# powerblade_v6_1_corr.net
KiCad netlist of a schematic drawn in EAGLE
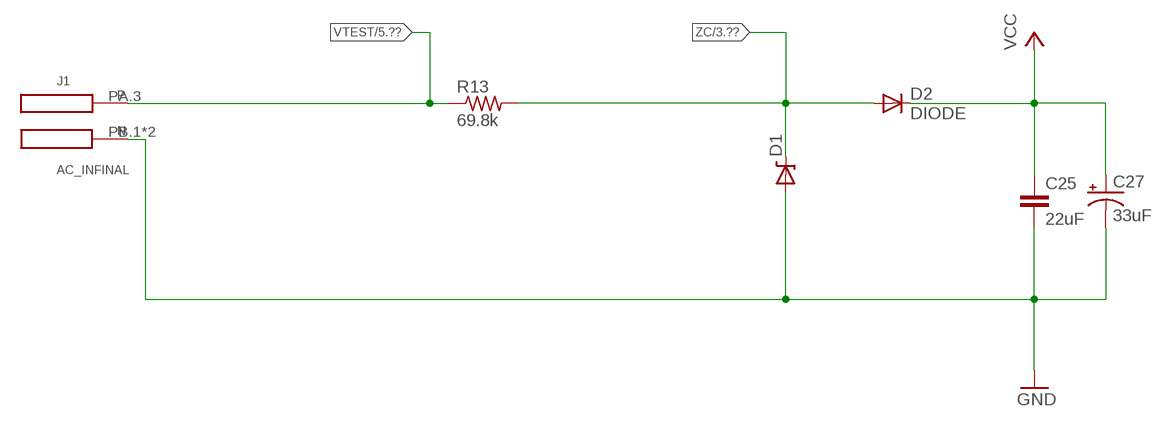
[diagram p0: schematic, sheet 1]
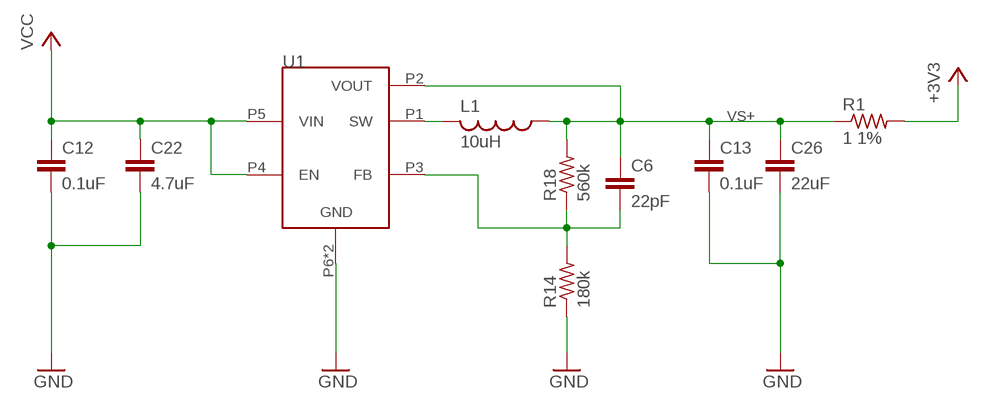
[diagram p1: schematic, sheet 2]
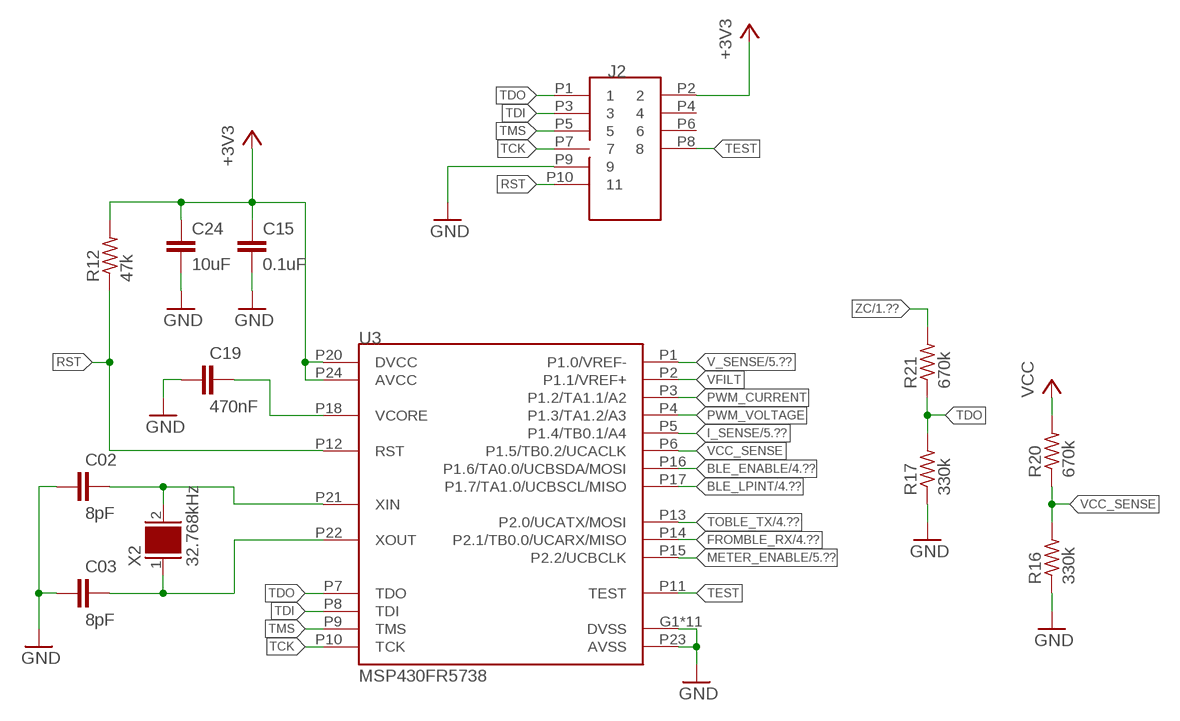
[diagram p2: schematic, sheet 3]
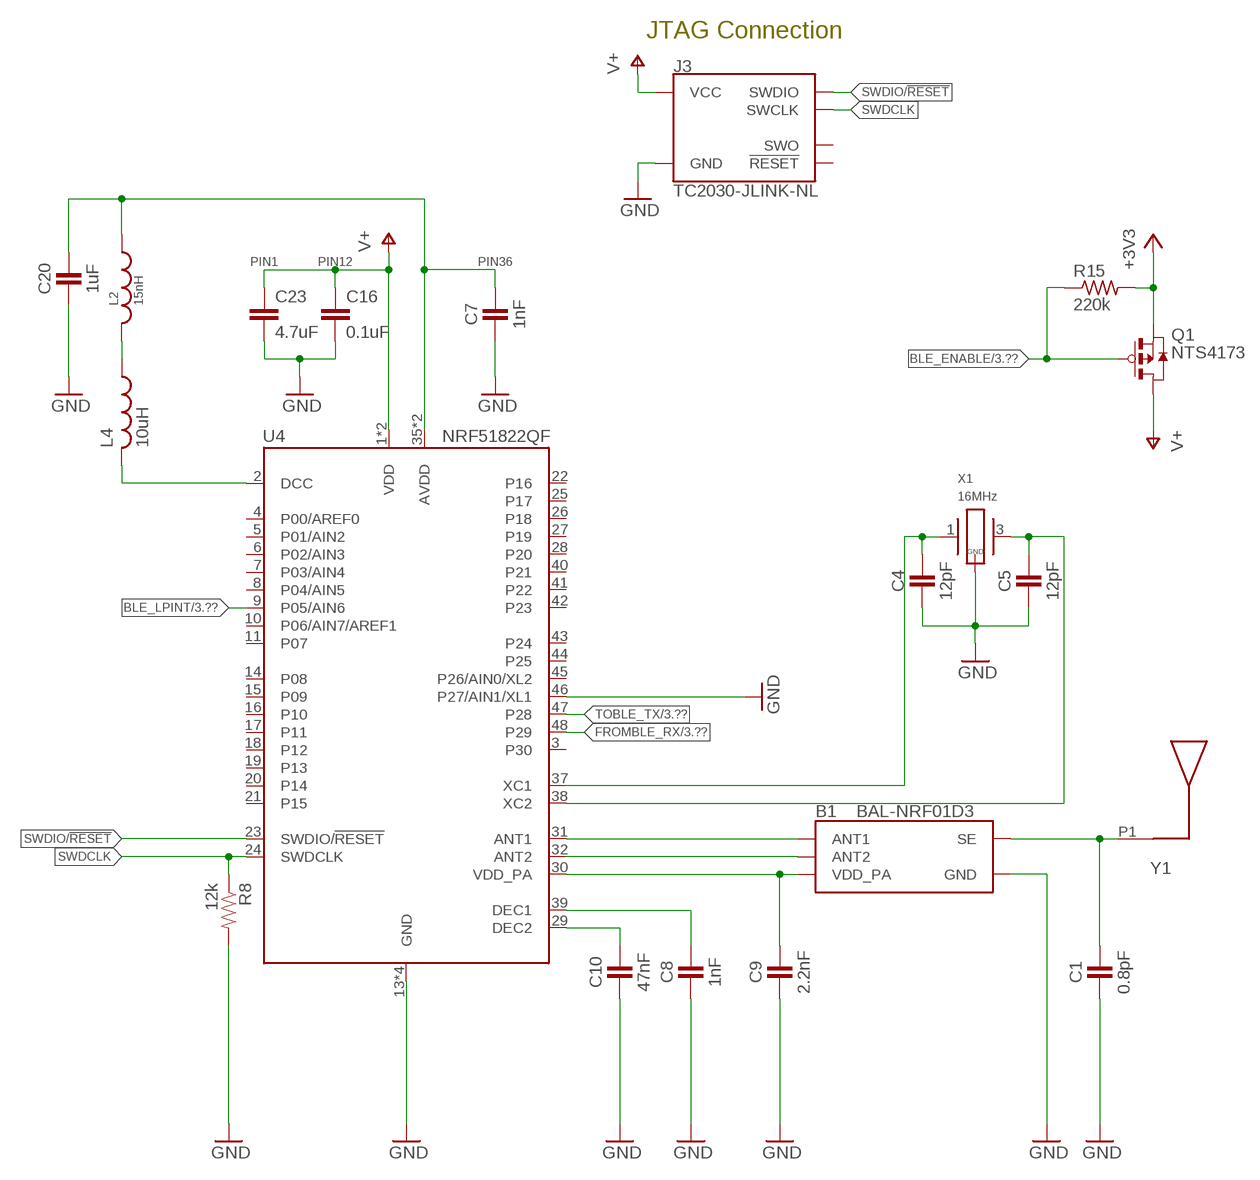
[diagram p3: schematic, sheet 4]
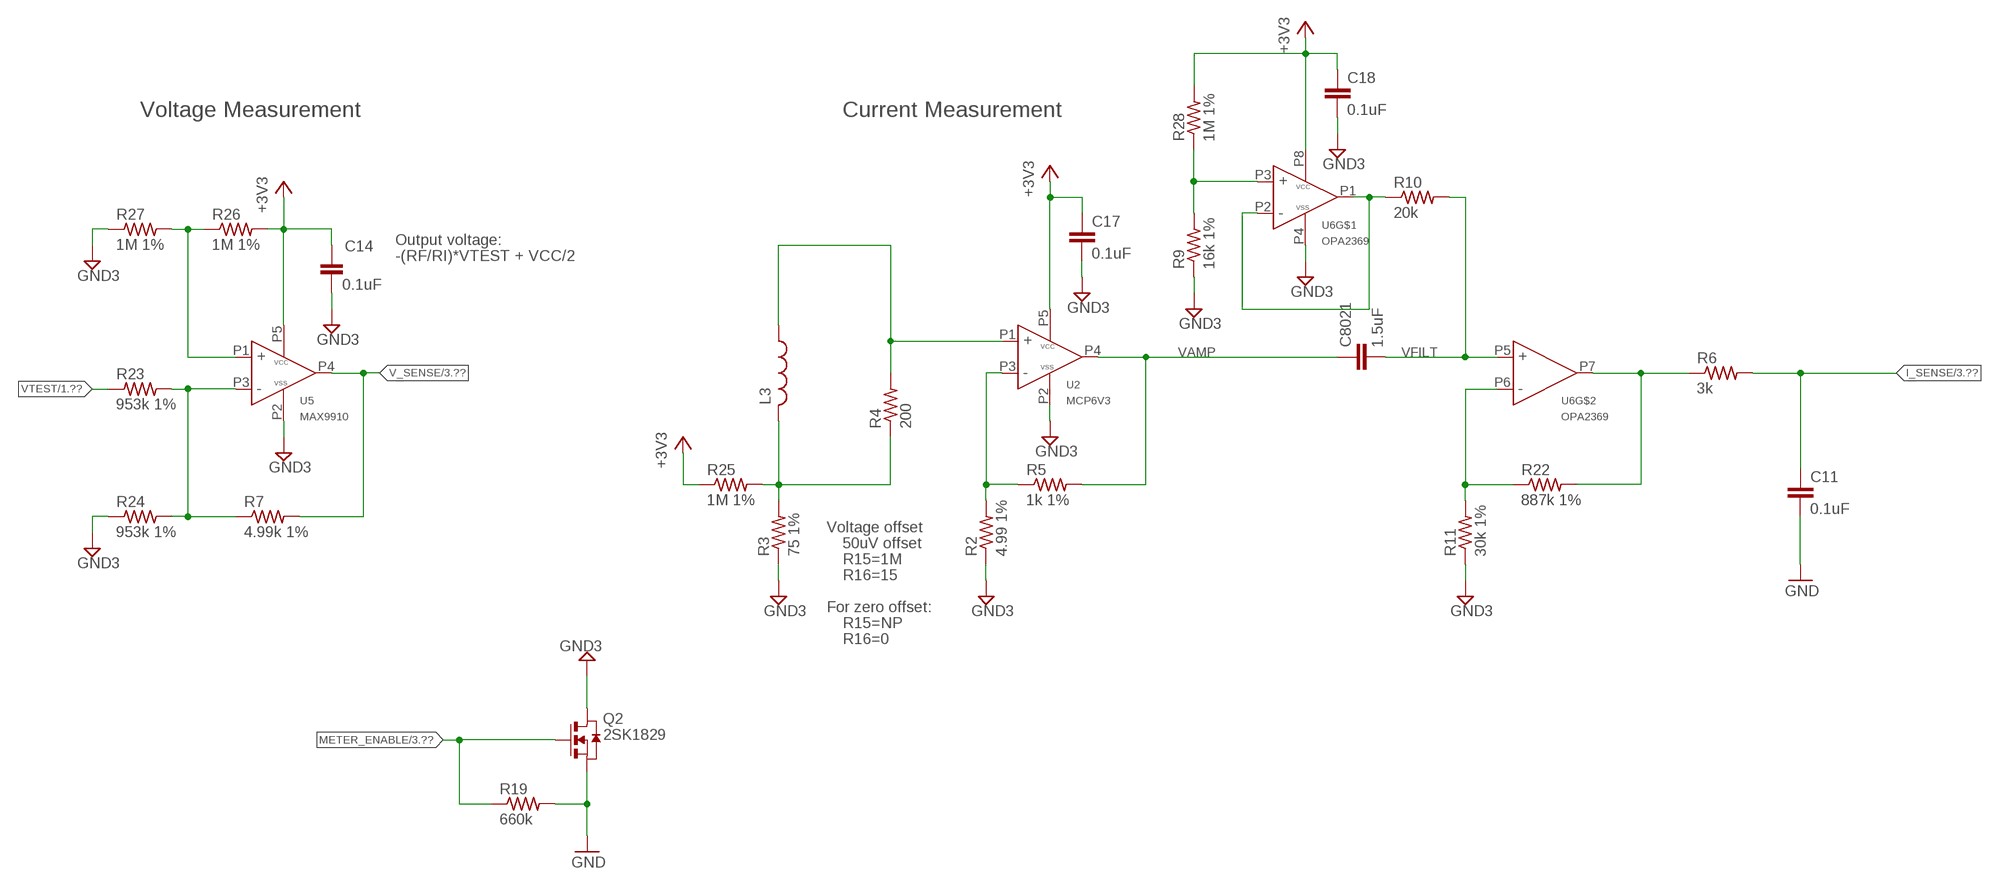
[diagram p4: schematic, sheet 5]

(export (version "E")
  (design (tool "Eeschema 10.0.6"))
  (components
    (comp (ref "C25")
      (value "22uF")
      (footprint "eagle-import:C0603_SM")
      (libsource (lib "eagle-import") (part "C-EUC0603_SM"))
    )
    (comp (ref "C27")
      (value "33uF")
      (footprint "eagle-import:CPOL0805_SM")
      (libsource (lib "eagle-import") (part "CPOL-US0805_SM"))
    )
    (comp (ref "D1")
      (value "ZENERBZT52")
      (footprint "eagle-import:BZT52")
      (fields (field (name "DIGIKEY") "BZT52C10T-7DICT-ND "))
      (libsource (lib "eagle-import") (part "ZENERBZT52"))
    )
    (comp (ref "D2")
      (value "DIODE")
      (footprint "eagle-import:BAS521")
      (libsource (lib "eagle-import") (part "DIODE"))
    )
    (comp (ref "J1")
      (value "AC_INFINAL")
      (footprint "eagle-import:AC3_FINAL")
      (libsource (lib "eagle-import") (part "AC_INFINAL"))
    )
    (comp (ref "R13")
      (value "69.8k")
      (footprint "eagle-import:R1210")
      (libsource (lib "eagle-import") (part "R-US_R1210"))
    )
    (comp (ref "B1")
      (value "BAL-NRF01D3")
      (footprint "eagle-import:BAL-NRF01D3")
      (libsource (lib "eagle-import") (part "BAL-NRF01D3"))
    )
    (comp (ref "C1")
      (value "0.8pF")
      (footprint "eagle-import:0402_CAP")
      (libsource (lib "eagle-import") (part "CAPACITOR"))
    )
    (comp (ref "C4")
      (value "12pF")
      (footprint "eagle-import:0402_CAP")
      (libsource (lib "eagle-import") (part "CAPACITOR"))
    )
    (comp (ref "C5")
      (value "12pF")
      (footprint "eagle-import:0402_CAP")
      (libsource (lib "eagle-import") (part "CAPACITOR"))
    )
    (comp (ref "C7")
      (value "1nF")
      (footprint "eagle-import:0402_CAP")
      (libsource (lib "eagle-import") (part "CAPACITOR"))
    )
    (comp (ref "C8")
      (value "1nF")
      (footprint "eagle-import:0402_CAP")
      (libsource (lib "eagle-import") (part "CAPACITOR"))
    )
    (comp (ref "C9")
      (value "2.2nF")
      (footprint "eagle-import:0402_CAP")
      (libsource (lib "eagle-import") (part "CAPACITOR"))
    )
    (comp (ref "C10")
      (value "47nF")
      (footprint "eagle-import:0402_CAP")
      (libsource (lib "eagle-import") (part "CAPACITOR"))
    )
    (comp (ref "C16")
      (value "0.1uF")
      (footprint "eagle-import:C0402")
      (libsource (lib "eagle-import") (part "C-EUC0402"))
    )
    (comp (ref "C20")
      (value "1uF")
      (footprint "eagle-import:0402_CAP")
      (libsource (lib "eagle-import") (part "CAPACITOR"))
    )
    (comp (ref "C23")
      (value "4.7uF")
      (footprint "eagle-import:C0402")
      (libsource (lib "eagle-import") (part "C-EUC0402"))
    )
    (comp (ref "J3")
      (value "TC2030-JLINK-NL")
      (footprint "eagle-import:TC2030-IDC-NL")
      (libsource (lib "eagle-import") (part "TC2030-JLINK-NL"))
    )
    (comp (ref "L2")
      (value "15nH")
      (footprint "eagle-import:0402_CAP")
      (libsource (lib "eagle-import") (part "INDUCTOR0402"))
    )
    (comp (ref "L4")
      (value "10uH")
      (footprint "eagle-import:C0603_TN")
      (libsource (lib "eagle-import") (part "L-USL0603_TN"))
    )
    (comp (ref "Q1")
      (value "NTS4173")
      (footprint "eagle-import:SC-70-3")
      (libsource (lib "eagle-import") (part "NTS4173"))
    )
    (comp (ref "R8")
      (value "12k")
      (footprint "eagle-import:0402_RES")
      (libsource (lib "eagle-import") (part "RESISTOR"))
    )
    (comp (ref "R15")
      (value "220k")
      (footprint "eagle-import:R0402_SM")
      (libsource (lib "eagle-import") (part "R-US_R0402_SM"))
    )
    (comp (ref "U4")
      (value "NRF51822QF")
      (footprint "eagle-import:QFN-48-6MM")
      (libsource (lib "eagle-import") (part "NRF51822QF"))
    )
    (comp (ref "X1")
      (value "16MHz")
      (footprint "eagle-import:TXC-8Y")
      (libsource (lib "eagle-import") (part "TXC-8Y"))
    )
    (comp (ref "Y1")
      (value "UREACH_XTEND")
      (footprint "eagle-import:UREACH_XTEND")
      (libsource (lib "eagle-import") (part "UREACH_XTEND"))
    )
    (comp (ref "C02")
      (value "8pF")
      (footprint "eagle-import:C0402")
      (libsource (lib "eagle-import") (part "C-EUC0402"))
    )
    (comp (ref "C03")
      (value "8pF")
      (footprint "eagle-import:C0402")
      (libsource (lib "eagle-import") (part "C-EUC0402"))
    )
    (comp (ref "C15")
      (value "0.1uF")
      (footprint "eagle-import:C0402")
      (libsource (lib "eagle-import") (part "C-EUC0402"))
    )
    (comp (ref "C19")
      (value "470nF")
      (footprint "eagle-import:C0402")
      (libsource (lib "eagle-import") (part "C-EUC0402"))
    )
    (comp (ref "C24")
      (value "10uF")
      (footprint "eagle-import:C0603_SM")
      (libsource (lib "eagle-import") (part "C-EUC0603_SM"))
    )
    (comp (ref "J2")
      (value "JTAG_14PIN_IDC-ND")
      (footprint "eagle-import:TC2050-IDC-NL-430-ND")
      (libsource (lib "eagle-import") (part "JTAG_14PIN_IDC-ND"))
    )
    (comp (ref "R12")
      (value "47k")
      (footprint "eagle-import:R0402")
      (libsource (lib "eagle-import") (part "R-US_R0402"))
    )
    (comp (ref "R16")
      (value "330k")
      (footprint "eagle-import:R0402")
      (libsource (lib "eagle-import") (part "R-US_R0402"))
    )
    (comp (ref "R17")
      (value "330k")
      (footprint "eagle-import:R0402")
      (libsource (lib "eagle-import") (part "R-US_R0402"))
    )
    (comp (ref "R20")
      (value "670k")
      (footprint "eagle-import:R0402")
      (libsource (lib "eagle-import") (part "R-US_R0402"))
    )
    (comp (ref "R21")
      (value "670k")
      (footprint "eagle-import:R0402")
      (libsource (lib "eagle-import") (part "R-US_R0402"))
    )
    (comp (ref "U3")
      (value "MSP430FR5738")
      (footprint "eagle-import:VQFN-24")
      (libsource (lib "eagle-import") (part "MSP430FR5738"))
    )
    (comp (ref "X2")
      (value "32.768kHz")
      (footprint "eagle-import:0805")
      (libsource (lib "eagle-import") (part "CRYSTAL_0805"))
    )
    (comp (ref "C11")
      (value "0.1uF")
      (footprint "eagle-import:C0402")
      (libsource (lib "eagle-import") (part "C-EUC0402"))
    )
    (comp (ref "C14")
      (value "0.1uF")
      (footprint "eagle-import:0402_CAP")
      (libsource (lib "eagle-import") (part "CAPACITOR"))
    )
    (comp (ref "C17")
      (value "0.1uF")
      (footprint "eagle-import:C0402")
      (libsource (lib "eagle-import") (part "C-EUC0402"))
    )
    (comp (ref "C18")
      (value "0.1uF")
      (footprint "eagle-import:C0402")
      (libsource (lib "eagle-import") (part "C-EUC0402"))
    )
    (comp (ref "C8021")
      (value "1.5uF")
      (footprint "eagle-import:C0402")
      (libsource (lib "eagle-import") (part "C-EUC0402"))
    )
    (comp (ref "L3")
      (value "L-USL0805")
      (footprint "eagle-import:L0805")
      (libsource (lib "eagle-import") (part "L-USL0805"))
    )
    (comp (ref "Q2")
      (value "2SK1829")
      (footprint "eagle-import:SC-70-3")
      (libsource (lib "eagle-import") (part "2SK1829"))
    )
    (comp (ref "R2")
      (value "4.99 1%")
      (footprint "eagle-import:R0402")
      (libsource (lib "eagle-import") (part "R-US_R0402"))
    )
    (comp (ref "R3")
      (value "75 1%")
      (footprint "eagle-import:R0402")
      (libsource (lib "eagle-import") (part "R-US_R0402"))
    )
    (comp (ref "R4")
      (value "200")
      (footprint "eagle-import:R0402")
      (libsource (lib "eagle-import") (part "R-US_R0402"))
    )
    (comp (ref "R5")
      (value "1k 1%")
      (footprint "eagle-import:R0402")
      (libsource (lib "eagle-import") (part "R-US_R0402"))
    )
    (comp (ref "R6")
      (value "3k")
      (footprint "eagle-import:R0402_SM")
      (libsource (lib "eagle-import") (part "R-US_R0402_SM"))
    )
    (comp (ref "R7")
      (value "4.99k 1%")
      (footprint "eagle-import:R0402")
      (libsource (lib "eagle-import") (part "R-US_R0402"))
    )
    (comp (ref "R9")
      (value "16k 1%")
      (footprint "eagle-import:R0402")
      (libsource (lib "eagle-import") (part "R-US_R0402"))
    )
    (comp (ref "R10")
      (value "20k")
      (footprint "eagle-import:R0402")
      (libsource (lib "eagle-import") (part "R-US_R0402"))
    )
    (comp (ref "R11")
      (value "30k 1%")
      (footprint "eagle-import:R0402")
      (libsource (lib "eagle-import") (part "R-US_R0402"))
    )
    (comp (ref "R19")
      (value "660k")
      (footprint "eagle-import:R0402")
      (libsource (lib "eagle-import") (part "R-US_R0402"))
    )
    (comp (ref "R22")
      (value "887k 1%")
      (footprint "eagle-import:R0402")
      (libsource (lib "eagle-import") (part "R-US_R0402"))
    )
    (comp (ref "R23")
      (value "953k 1%")
      (footprint "eagle-import:R0402")
      (libsource (lib "eagle-import") (part "R-US_R0402"))
    )
    (comp (ref "R24")
      (value "953k 1%")
      (footprint "eagle-import:R0402")
      (libsource (lib "eagle-import") (part "R-US_R0402"))
    )
    (comp (ref "R25")
      (value "1M 1%")
      (footprint "eagle-import:R0402")
      (libsource (lib "eagle-import") (part "R-US_R0402"))
    )
    (comp (ref "R26")
      (value "1M 1%")
      (footprint "eagle-import:R0402")
      (libsource (lib "eagle-import") (part "R-US_R0402"))
    )
    (comp (ref "R27")
      (value "1M 1%")
      (footprint "eagle-import:R0402_SM")
      (libsource (lib "eagle-import") (part "R-US_R0402_SM"))
    )
    (comp (ref "R28")
      (value "1M 1%")
      (footprint "eagle-import:R0402")
      (libsource (lib "eagle-import") (part "R-US_R0402"))
    )
    (comp (ref "U2")
      (value "MCP6V3")
      (footprint "eagle-import:SC70-5")
      (fields (field (name "DIGIKEY") "296-19547-1-ND"))
      (libsource (lib "eagle-import") (part "MCP6V3"))
    )
    (comp (ref "U5")
      (value "MAX9910")
      (footprint "eagle-import:SC70-5")
      (fields (field (name "DIGIKEY") "296-25252-1-ND"))
      (libsource (lib "eagle-import") (part "MAX9910"))
    )
    (comp (ref "U6")
      (value "OPA2369")
      (footprint "eagle-import:SOT-23-8")
      (libsource (lib "eagle-import") (part "OPA2369"))
    )
    (comp (ref "C6")
      (value "22pF")
      (footprint "eagle-import:C0402")
      (libsource (lib "eagle-import") (part "C-EUC0402"))
    )
    (comp (ref "C12")
      (value "0.1uF")
      (footprint "eagle-import:C0402")
      (libsource (lib "eagle-import") (part "C-EUC0402"))
    )
    (comp (ref "C13")
      (value "0.1uF")
      (footprint "eagle-import:C0402_SM")
      (libsource (lib "eagle-import") (part "C-EUC0402_SM"))
    )
    (comp (ref "C22")
      (value "4.7uF")
      (footprint "eagle-import:C0402")
      (libsource (lib "eagle-import") (part "C-EUC0402"))
    )
    (comp (ref "C26")
      (value "22uF")
      (footprint "eagle-import:C0603_SM")
      (libsource (lib "eagle-import") (part "C-EUC0603_SM"))
    )
    (comp (ref "L1")
      (value "10uH")
      (footprint "eagle-import:L0805")
      (libsource (lib "eagle-import") (part "L-USL0805"))
    )
    (comp (ref "R1")
      (value "1 1%")
      (footprint "eagle-import:R0603_SM")
      (libsource (lib "eagle-import") (part "R-US_R0603_SM"))
    )
    (comp (ref "R14")
      (value "180k")
      (footprint "eagle-import:R0402")
      (libsource (lib "eagle-import") (part "R-US_R0402"))
    )
    (comp (ref "R18")
      (value "560k")
      (footprint "eagle-import:R0402")
      (libsource (lib "eagle-import") (part "R-US_R0402"))
    )
    (comp (ref "U1")
      (value "TPS62122")
      (footprint "eagle-import:WDFN-6")
      (libsource (lib "eagle-import") (part "TPS62122"))
    )
  )
  (nets
    (net (code "1") (name "+3V3") (class "Default")
      (node (ref "C14") (pin "1") (pinfunction "1_1") (pintype "bidirectional"))
      (node (ref "C15") (pin "1") (pinfunction "1_1") (pintype "passive"))
      (node (ref "C17") (pin "1") (pinfunction "1_1") (pintype "passive"))
      (node (ref "C18") (pin "1") (pinfunction "1_1") (pintype "passive"))
      (node (ref "C24") (pin "1") (pinfunction "1_1") (pintype "passive"))
      (node (ref "J2") (pin "P2") (pinfunction "2_P2") (pintype "bidirectional"))
      (node (ref "Q1") (pin "P2") (pinfunction "S_P2") (pintype "passive"))
      (node (ref "R1") (pin "2") (pinfunction "2_2") (pintype "passive"))
      (node (ref "R12") (pin "2") (pinfunction "2_2") (pintype "passive"))
      (node (ref "R15") (pin "2") (pinfunction "2_2") (pintype "passive"))
      (node (ref "R25") (pin "1") (pinfunction "1_1") (pintype "passive"))
      (node (ref "R26") (pin "2") (pinfunction "2_2") (pintype "passive"))
      (node (ref "R28") (pin "2") (pinfunction "2_2") (pintype "passive"))
      (node (ref "U2") (pin "P5") (pinfunction "VCC_P5") (pintype "bidirectional"))
      (node (ref "U3") (pin "P20") (pinfunction "DVCC_P20") (pintype "bidirectional"))
      (node (ref "U3") (pin "P24") (pinfunction "AVCC_P24") (pintype "bidirectional"))
      (node (ref "U5") (pin "P5") (pinfunction "VCC_P5") (pintype "bidirectional"))
      (node (ref "U6") (pin "P8") (pinfunction "VCC_P8") (pintype "bidirectional"))
    )
    (net (code "2") (name "BLE_ENABLE") (class "Default")
      (node (ref "Q1") (pin "P1") (pinfunction "G_P1") (pintype "passive"))
      (node (ref "R15") (pin "1") (pinfunction "1_1") (pintype "passive"))
      (node (ref "U3") (pin "P16") (pinfunction "P1.6/TA0.0/UCBSDA/MOSI_P16") (pintype "bidirectional"))
    )
    (net (code "3") (name "BLE_LPINT") (class "Default")
      (node (ref "U3") (pin "P17") (pinfunction "P1.7/TA1.0/UCBSCL/MISO_P17") (pintype "bidirectional"))
      (node (ref "U4") (pin "9") (pinfunction "P05/AIN6_9") (pintype "bidirectional"))
    )
    (net (code "4") (name "FROMBLE_RX") (class "Default")
      (node (ref "U3") (pin "P14") (pinfunction "P2.1/TB0.0/UCARX/MISO_P14") (pintype "bidirectional"))
      (node (ref "U4") (pin "48") (pinfunction "P29_48") (pintype "bidirectional"))
    )
    (net (code "5") (name "GND") (class "Default")
      (node (ref "B1") (pin "GND") (pinfunction "GND_GND") (pintype "bidirectional"))
      (node (ref "C02") (pin "1") (pinfunction "1_1") (pintype "passive"))
      (node (ref "C03") (pin "1") (pinfunction "1_1") (pintype "passive"))
      (node (ref "C1") (pin "2") (pinfunction "2_2") (pintype "bidirectional"))
      (node (ref "C10") (pin "2") (pinfunction "2_2") (pintype "bidirectional"))
      (node (ref "C11") (pin "2") (pinfunction "2_2") (pintype "passive"))
      (node (ref "C12") (pin "2") (pinfunction "2_2") (pintype "passive"))
      (node (ref "C13") (pin "2") (pinfunction "2_2") (pintype "passive"))
      (node (ref "C15") (pin "2") (pinfunction "2_2") (pintype "passive"))
      (node (ref "C16") (pin "2") (pinfunction "2_2") (pintype "passive"))
      (node (ref "C19") (pin "1") (pinfunction "1_1") (pintype "passive"))
      (node (ref "C20") (pin "2") (pinfunction "2_2") (pintype "bidirectional"))
      (node (ref "C22") (pin "2") (pinfunction "2_2") (pintype "passive"))
      (node (ref "C23") (pin "2") (pinfunction "2_2") (pintype "passive"))
      (node (ref "C24") (pin "2") (pinfunction "2_2") (pintype "passive"))
      (node (ref "C25") (pin "2") (pinfunction "2_2") (pintype "passive"))
      (node (ref "C26") (pin "2") (pinfunction "2_2") (pintype "passive"))
      (node (ref "C27") (pin "-") (pinfunction "-_-") (pintype "passive"))
      (node (ref "C4") (pin "2") (pinfunction "2_2") (pintype "bidirectional"))
      (node (ref "C5") (pin "2") (pinfunction "2_2") (pintype "bidirectional"))
      (node (ref "C7") (pin "2") (pinfunction "2_2") (pintype "bidirectional"))
      (node (ref "C8") (pin "2") (pinfunction "2_2") (pintype "bidirectional"))
      (node (ref "C9") (pin "2") (pinfunction "2_2") (pintype "bidirectional"))
      (node (ref "D1") (pin "A") (pinfunction "A_A") (pintype "passive"))
      (node (ref "J1") (pin "PB.1") (pinfunction "N_PB.1") (pintype "bidirectional"))
      (node (ref "J1") (pin "PB.3") (pinfunction "N_PB.3") (pintype "bidirectional"))
      (node (ref "J2") (pin "P9") (pinfunction "9_P9") (pintype "bidirectional"))
      (node (ref "J3") (pin "5") (pinfunction "GND_5") (pintype "bidirectional"))
      (node (ref "Q2") (pin "P2") (pinfunction "S_P2") (pintype "passive"))
      (node (ref "R14") (pin "1") (pinfunction "1_1") (pintype "passive"))
      (node (ref "R16") (pin "1") (pinfunction "1_1") (pintype "passive"))
      (node (ref "R17") (pin "1") (pinfunction "1_1") (pintype "passive"))
      (node (ref "R19") (pin "2") (pinfunction "2_2") (pintype "passive"))
      (node (ref "R8") (pin "2") (pinfunction "2_2") (pintype "passive"))
      (node (ref "U1") (pin "P6") (pinfunction "GND_P6") (pintype "bidirectional"))
      (node (ref "U1") (pin "PAD") (pinfunction "GND_PAD") (pintype "bidirectional"))
      (node (ref "U3") (pin "G1") (pinfunction "DVSS_G1") (pintype "bidirectional"))
      (node (ref "U3") (pin "G2") (pinfunction "DVSS_G2") (pintype "bidirectional"))
      (node (ref "U3") (pin "G3") (pinfunction "DVSS_G3") (pintype "bidirectional"))
      (node (ref "U3") (pin "G4") (pinfunction "DVSS_G4") (pintype "bidirectional"))
      (node (ref "U3") (pin "G5") (pinfunction "DVSS_G5") (pintype "bidirectional"))
      (node (ref "U3") (pin "G6") (pinfunction "DVSS_G6") (pintype "bidirectional"))
      (node (ref "U3") (pin "G7") (pinfunction "DVSS_G7") (pintype "bidirectional"))
      (node (ref "U3") (pin "G8") (pinfunction "DVSS_G8") (pintype "bidirectional"))
      (node (ref "U3") (pin "G9") (pinfunction "DVSS_G9") (pintype "bidirectional"))
      (node (ref "U3") (pin "P19") (pinfunction "DVSS_P19") (pintype "bidirectional"))
      (node (ref "U3") (pin "P23") (pinfunction "AVSS_P23") (pintype "bidirectional"))
      (node (ref "U3") (pin "PAD") (pinfunction "DVSS_PAD") (pintype "bidirectional"))
      (node (ref "U4") (pin "13") (pinfunction "GND_13") (pintype "bidirectional"))
      (node (ref "U4") (pin "33") (pinfunction "GND_33") (pintype "bidirectional"))
      (node (ref "U4") (pin "34") (pinfunction "GND_34") (pintype "bidirectional"))
      (node (ref "U4") (pin "46") (pinfunction "P27/AIN1/XL1_46") (pintype "bidirectional"))
      (node (ref "U4") (pin "GND") (pinfunction "GND_GND") (pintype "bidirectional"))
      (node (ref "X1") (pin "2") (pinfunction "GND_2") (pintype "bidirectional"))
      (node (ref "X1") (pin "4") (pinfunction "GND_4") (pintype "bidirectional"))
    )
    (net (code "6") (name "GND3") (class "Default")
      (node (ref "C14") (pin "2") (pinfunction "2_2") (pintype "bidirectional"))
      (node (ref "C17") (pin "2") (pinfunction "2_2") (pintype "passive"))
      (node (ref "C18") (pin "2") (pinfunction "2_2") (pintype "passive"))
      (node (ref "Q2") (pin "P3") (pinfunction "D_P3") (pintype "passive"))
      (node (ref "R11") (pin "1") (pinfunction "1_1") (pintype "passive"))
      (node (ref "R2") (pin "1") (pinfunction "1_1") (pintype "passive"))
      (node (ref "R24") (pin "1") (pinfunction "1_1") (pintype "passive"))
      (node (ref "R27") (pin "1") (pinfunction "1_1") (pintype "passive"))
      (node (ref "R3") (pin "1") (pinfunction "1_1") (pintype "passive"))
      (node (ref "R9") (pin "1") (pinfunction "1_1") (pintype "passive"))
      (node (ref "U2") (pin "P2") (pinfunction "VSS_P2") (pintype "bidirectional"))
      (node (ref "U5") (pin "P2") (pinfunction "VSS_P2") (pintype "bidirectional"))
      (node (ref "U6") (pin "P4") (pinfunction "VSS_P4") (pintype "bidirectional"))
    )
    (net (code "7") (name "I_SENSE") (class "Default")
      (node (ref "C11") (pin "1") (pinfunction "1_1") (pintype "passive"))
      (node (ref "R6") (pin "2") (pinfunction "2_2") (pintype "passive"))
      (node (ref "U3") (pin "P5") (pinfunction "P1.4/TB0.1/A4_P5") (pintype "bidirectional"))
    )
    (net (code "8") (name "METER_ENABLE") (class "Default")
      (node (ref "Q2") (pin "P1") (pinfunction "G_P1") (pintype "passive"))
      (node (ref "R19") (pin "1") (pinfunction "1_1") (pintype "passive"))
      (node (ref "U3") (pin "P15") (pinfunction "P2.2/UCBCLK_P15") (pintype "bidirectional"))
    )
    (net (code "9") (name "Net-(B1-PadSE)") (class "Default")
      (node (ref "B1") (pin "SE") (pinfunction "SE_SE") (pintype "bidirectional"))
      (node (ref "C1") (pin "1") (pinfunction "1_1") (pintype "bidirectional"))
      (node (ref "Y1") (pin "P1") (pinfunction "P1_P1") (pintype "bidirectional"))
    )
    (net (code "10") (name "Net-(B1-VDD_PA)") (class "Default")
      (node (ref "B1") (pin "VCC") (pinfunction "VDD_PA_VCC") (pintype "bidirectional"))
      (node (ref "C9") (pin "1") (pinfunction "1_1") (pintype "bidirectional"))
      (node (ref "U4") (pin "30") (pinfunction "VDD_PA_30") (pintype "bidirectional"))
    )
    (net (code "11") (name "Net-(C20-Pad1)") (class "Default")
      (node (ref "C20") (pin "1") (pinfunction "1_1") (pintype "bidirectional"))
      (node (ref "C7") (pin "1") (pinfunction "1_1") (pintype "bidirectional"))
      (node (ref "L2") (pin "1") (pinfunction "1_1") (pintype "bidirectional"))
      (node (ref "U4") (pin "35") (pinfunction "AVDD_35") (pintype "bidirectional"))
      (node (ref "U4") (pin "36") (pinfunction "AVDD_36") (pintype "bidirectional"))
    )
    (net (code "12") (name "Net-(L2-Pad2)") (class "Default")
      (node (ref "L2") (pin "2") (pinfunction "2_2") (pintype "bidirectional"))
      (node (ref "L4") (pin "1") (pinfunction "1_1") (pintype "passive"))
    )
    (net (code "13") (name "Net-(L3-Pad2)") (class "Default")
      (node (ref "L3") (pin "2") (pinfunction "2_2") (pintype "passive"))
      (node (ref "R25") (pin "2") (pinfunction "2_2") (pintype "passive"))
      (node (ref "R3") (pin "2") (pinfunction "2_2") (pintype "passive"))
      (node (ref "R4") (pin "1") (pinfunction "1_1") (pintype "passive"))
    )
    (net (code "14") (name "Net-(U1-FB)") (class "Default")
      (node (ref "C6") (pin "2") (pinfunction "2_2") (pintype "passive"))
      (node (ref "R14") (pin "2") (pinfunction "2_2") (pintype "passive"))
      (node (ref "R18") (pin "1") (pinfunction "1_1") (pintype "passive"))
      (node (ref "U1") (pin "P3") (pinfunction "FB_P3") (pintype "bidirectional"))
    )
    (net (code "15") (name "Net-(U1-SW)") (class "Default")
      (node (ref "L1") (pin "2") (pinfunction "2_2") (pintype "passive"))
      (node (ref "U1") (pin "P1") (pinfunction "SW_P1") (pintype "bidirectional"))
    )
    (net (code "16") (name "Net-(U2-IN+)") (class "Default")
      (node (ref "L3") (pin "1") (pinfunction "1_1") (pintype "passive"))
      (node (ref "R4") (pin "2") (pinfunction "2_2") (pintype "passive"))
      (node (ref "U2") (pin "P1") (pinfunction "IN+_P1") (pintype "bidirectional"))
    )
    (net (code "17") (name "Net-(U2-IN-)") (class "Default")
      (node (ref "R2") (pin "2") (pinfunction "2_2") (pintype "passive"))
      (node (ref "R5") (pin "1") (pinfunction "1_1") (pintype "passive"))
      (node (ref "U2") (pin "P3") (pinfunction "IN-_P3") (pintype "bidirectional"))
    )
    (net (code "18") (name "Net-(U3-VCORE)") (class "Default")
      (node (ref "C19") (pin "2") (pinfunction "2_2") (pintype "passive"))
      (node (ref "U3") (pin "P18") (pinfunction "VCORE_P18") (pintype "bidirectional"))
    )
    (net (code "19") (name "Net-(U3-XIN)") (class "Default")
      (node (ref "C02") (pin "2") (pinfunction "2_2") (pintype "passive"))
      (node (ref "U3") (pin "P21") (pinfunction "XIN_P21") (pintype "bidirectional"))
      (node (ref "X2") (pin "2") (pinfunction "P2_2") (pintype "bidirectional"))
    )
    (net (code "20") (name "Net-(U3-XOUT)") (class "Default")
      (node (ref "C03") (pin "2") (pinfunction "2_2") (pintype "passive"))
      (node (ref "U3") (pin "P22") (pinfunction "XOUT_P22") (pintype "bidirectional"))
      (node (ref "X2") (pin "1") (pinfunction "P1_1") (pintype "bidirectional"))
    )
    (net (code "21") (name "Net-(U4-ANT1)") (class "Default")
      (node (ref "B1") (pin "ANT1") (pinfunction "ANT1_ANT1") (pintype "bidirectional"))
      (node (ref "U4") (pin "31") (pinfunction "ANT1_31") (pintype "bidirectional"))
    )
    (net (code "22") (name "Net-(U4-ANT2)") (class "Default")
      (node (ref "B1") (pin "ANT2") (pinfunction "ANT2_ANT2") (pintype "bidirectional"))
      (node (ref "U4") (pin "32") (pinfunction "ANT2_32") (pintype "bidirectional"))
    )
    (net (code "23") (name "Net-(U4-DCC)") (class "Default")
      (node (ref "L4") (pin "2") (pinfunction "2_2") (pintype "passive"))
      (node (ref "U4") (pin "2") (pinfunction "DCC_2") (pintype "bidirectional"))
    )
    (net (code "24") (name "Net-(U4-DEC1)") (class "Default")
      (node (ref "C8") (pin "1") (pinfunction "1_1") (pintype "bidirectional"))
      (node (ref "U4") (pin "39") (pinfunction "DEC1_39") (pintype "bidirectional"))
    )
    (net (code "25") (name "Net-(U4-DEC2)") (class "Default")
      (node (ref "C10") (pin "1") (pinfunction "1_1") (pintype "bidirectional"))
      (node (ref "U4") (pin "29") (pinfunction "DEC2_29") (pintype "bidirectional"))
    )
    (net (code "26") (name "Net-(U4-XC1)") (class "Default")
      (node (ref "C4") (pin "1") (pinfunction "1_1") (pintype "bidirectional"))
      (node (ref "U4") (pin "37") (pinfunction "XC1_37") (pintype "bidirectional"))
      (node (ref "X1") (pin "1") (pinfunction "1_1") (pintype "bidirectional"))
    )
    (net (code "27") (name "Net-(U4-XC2)") (class "Default")
      (node (ref "C5") (pin "1") (pinfunction "1_1") (pintype "bidirectional"))
      (node (ref "U4") (pin "38") (pinfunction "XC2_38") (pintype "bidirectional"))
      (node (ref "X1") (pin "3") (pinfunction "2_3") (pintype "bidirectional"))
    )
    (net (code "28") (name "Net-(U5-IN+)") (class "Default")
      (node (ref "R26") (pin "1") (pinfunction "1_1") (pintype "passive"))
      (node (ref "R27") (pin "2") (pinfunction "2_2") (pintype "passive"))
      (node (ref "U5") (pin "P1") (pinfunction "IN+_P1") (pintype "bidirectional"))
    )
    (net (code "29") (name "Net-(U5-IN-)") (class "Default")
      (node (ref "R23") (pin "2") (pinfunction "2_2") (pintype "passive"))
      (node (ref "R24") (pin "2") (pinfunction "2_2") (pintype "passive"))
      (node (ref "R7") (pin "1") (pinfunction "1_1") (pintype "passive"))
      (node (ref "U5") (pin "P3") (pinfunction "IN-_P3") (pintype "bidirectional"))
    )
    (net (code "30") (name "Net-(U6A-IN+)") (class "Default")
      (node (ref "R28") (pin "1") (pinfunction "1_1") (pintype "passive"))
      (node (ref "R9") (pin "2") (pinfunction "2_2") (pintype "passive"))
      (node (ref "U6") (pin "P3") (pinfunction "IN+_P3") (pintype "bidirectional"))
    )
    (net (code "31") (name "Net-(U6A-IN-)") (class "Default")
      (node (ref "R10") (pin "1") (pinfunction "1_1") (pintype "passive"))
      (node (ref "U6") (pin "P1") (pinfunction "OUT_P1") (pintype "bidirectional"))
      (node (ref "U6") (pin "P2") (pinfunction "IN-_P2") (pintype "bidirectional"))
    )
    (net (code "32") (name "Net-(U6B-IN-)") (class "Default")
      (node (ref "R11") (pin "2") (pinfunction "2_2") (pintype "passive"))
      (node (ref "R22") (pin "1") (pinfunction "1_1") (pintype "passive"))
      (node (ref "U6") (pin "P6") (pinfunction "IN-_P6") (pintype "bidirectional"))
    )
    (net (code "33") (name "Net-(U6B-OUT)") (class "Default")
      (node (ref "R22") (pin "2") (pinfunction "2_2") (pintype "passive"))
      (node (ref "R6") (pin "1") (pinfunction "1_1") (pintype "passive"))
      (node (ref "U6") (pin "P7") (pinfunction "OUT_P7") (pintype "bidirectional"))
    )
    (net (code "34") (name "PWM_CURRENT") (class "Default")
      (node (ref "U3") (pin "P3") (pinfunction "P1.2/TA1.1/A2_P3") (pintype "bidirectional"))
    )
    (net (code "35") (name "PWM_VOLTAGE") (class "Default")
      (node (ref "U3") (pin "P4") (pinfunction "P1.3/TA1.2/A3_P4") (pintype "bidirectional"))
    )
    (net (code "36") (name "RST") (class "Default")
      (node (ref "J2") (pin "P10") (pinfunction "11_P10") (pintype "bidirectional"))
      (node (ref "R12") (pin "1") (pinfunction "1_1") (pintype "passive"))
      (node (ref "U3") (pin "P12") (pinfunction "RST_P12") (pintype "bidirectional"))
    )
    (net (code "37") (name "SWDCLK") (class "Default")
      (node (ref "J3") (pin "4") (pinfunction "SWCLK_4") (pintype "bidirectional"))
      (node (ref "R8") (pin "1") (pinfunction "1_1") (pintype "passive"))
      (node (ref "U4") (pin "24") (pinfunction "SWDCLK_24") (pintype "bidirectional"))
    )
    (net (code "38") (name "SWDIO{slash}~{RESET}") (class "Default")
      (node (ref "J3") (pin "2") (pinfunction "SWDIO_2") (pintype "bidirectional"))
      (node (ref "U4") (pin "23") (pinfunction "SWDIO/~{RESET}_23") (pintype "bidirectional"))
    )
    (net (code "39") (name "TCK") (class "Default")
      (node (ref "J2") (pin "P7") (pinfunction "7_P7") (pintype "bidirectional"))
      (node (ref "U3") (pin "P10") (pinfunction "TCK_P10") (pintype "bidirectional"))
    )
    (net (code "40") (name "TDI") (class "Default")
      (node (ref "J2") (pin "P3") (pinfunction "3_P3") (pintype "bidirectional"))
      (node (ref "U3") (pin "P8") (pinfunction "TDI_P8") (pintype "bidirectional"))
    )
    (net (code "41") (name "TDO") (class "Default")
      (node (ref "J2") (pin "P1") (pinfunction "1_P1") (pintype "bidirectional"))
      (node (ref "R17") (pin "2") (pinfunction "2_2") (pintype "passive"))
      (node (ref "R21") (pin "1") (pinfunction "1_1") (pintype "passive"))
      (node (ref "U3") (pin "P7") (pinfunction "TDO_P7") (pintype "bidirectional"))
    )
    (net (code "42") (name "TEST") (class "Default")
      (node (ref "J2") (pin "P8") (pinfunction "8_P8") (pintype "bidirectional"))
      (node (ref "U3") (pin "P11") (pinfunction "TEST_P11") (pintype "bidirectional"))
    )
    (net (code "43") (name "TMS") (class "Default")
      (node (ref "J2") (pin "P5") (pinfunction "5_P5") (pintype "bidirectional"))
      (node (ref "U3") (pin "P9") (pinfunction "TMS_P9") (pintype "bidirectional"))
    )
    (net (code "44") (name "TOBLE_TX") (class "Default")
      (node (ref "U3") (pin "P13") (pinfunction "P2.0/UCATX/MOSI_P13") (pintype "bidirectional"))
      (node (ref "U4") (pin "47") (pinfunction "P28_47") (pintype "bidirectional"))
    )
    (net (code "45") (name "V+") (class "Default")
      (node (ref "C16") (pin "1") (pinfunction "1_1") (pintype "passive"))
      (node (ref "C23") (pin "1") (pinfunction "1_1") (pintype "passive"))
      (node (ref "J3") (pin "1") (pinfunction "VCC_1") (pintype "bidirectional"))
      (node (ref "Q1") (pin "P3") (pinfunction "D_P3") (pintype "passive"))
      (node (ref "U4") (pin "1") (pinfunction "VDD_1") (pintype "bidirectional"))
      (node (ref "U4") (pin "12") (pinfunction "VDD_12") (pintype "bidirectional"))
    )
    (net (code "46") (name "VAMP") (class "Default")
      (node (ref "C8021") (pin "1") (pinfunction "1_1") (pintype "passive"))
      (node (ref "R5") (pin "2") (pinfunction "2_2") (pintype "passive"))
      (node (ref "U2") (pin "P4") (pinfunction "OUT_P4") (pintype "bidirectional"))
    )
    (net (code "47") (name "VCC") (class "Default")
      (node (ref "C12") (pin "1") (pinfunction "1_1") (pintype "passive"))
      (node (ref "C22") (pin "1") (pinfunction "1_1") (pintype "passive"))
      (node (ref "C25") (pin "1") (pinfunction "1_1") (pintype "passive"))
      (node (ref "C27") (pin "+") (pinfunction "+_+") (pintype "passive"))
      (node (ref "D2") (pin "C") (pinfunction "C_C") (pintype "passive"))
      (node (ref "R20") (pin "2") (pinfunction "2_2") (pintype "passive"))
      (node (ref "U1") (pin "P4") (pinfunction "EN_P4") (pintype "bidirectional"))
      (node (ref "U1") (pin "P5") (pinfunction "VIN_P5") (pintype "bidirectional"))
    )
    (net (code "48") (name "VCC_SENSE") (class "Default")
      (node (ref "R16") (pin "2") (pinfunction "2_2") (pintype "passive"))
      (node (ref "R20") (pin "1") (pinfunction "1_1") (pintype "passive"))
      (node (ref "U3") (pin "P6") (pinfunction "P1.5/TB0.2/UCACLK_P6") (pintype "bidirectional"))
    )
    (net (code "49") (name "VFILT") (class "Default")
      (node (ref "C8021") (pin "2") (pinfunction "2_2") (pintype "passive"))
      (node (ref "R10") (pin "2") (pinfunction "2_2") (pintype "passive"))
      (node (ref "U3") (pin "P2") (pinfunction "P1.1/VREF+_P2") (pintype "bidirectional"))
      (node (ref "U6") (pin "P5") (pinfunction "IN+_P5") (pintype "bidirectional"))
    )
    (net (code "50") (name "VS+") (class "Default")
      (node (ref "C13") (pin "1") (pinfunction "1_1") (pintype "passive"))
      (node (ref "C26") (pin "1") (pinfunction "1_1") (pintype "passive"))
      (node (ref "C6") (pin "1") (pinfunction "1_1") (pintype "passive"))
      (node (ref "L1") (pin "1") (pinfunction "1_1") (pintype "passive"))
      (node (ref "R1") (pin "1") (pinfunction "1_1") (pintype "passive"))
      (node (ref "R18") (pin "2") (pinfunction "2_2") (pintype "passive"))
      (node (ref "U1") (pin "P2") (pinfunction "VOUT_P2") (pintype "bidirectional"))
    )
    (net (code "51") (name "VTEST") (class "Default")
      (node (ref "J1") (pin "PA.3") (pinfunction "P_PA.3") (pintype "bidirectional"))
      (node (ref "R13") (pin "1") (pinfunction "1_1") (pintype "passive"))
      (node (ref "R23") (pin "1") (pinfunction "1_1") (pintype "passive"))
    )
    (net (code "52") (name "V_SENSE") (class "Default")
      (node (ref "R7") (pin "2") (pinfunction "2_2") (pintype "passive"))
      (node (ref "U3") (pin "P1") (pinfunction "P1.0/VREF-_P1") (pintype "bidirectional"))
      (node (ref "U5") (pin "P4") (pinfunction "OUT_P4") (pintype "bidirectional"))
    )
    (net (code "53") (name "ZC") (class "Default")
      (node (ref "D1") (pin "C") (pinfunction "C_C") (pintype "passive"))
      (node (ref "D2") (pin "A") (pinfunction "A_A") (pintype "passive"))
      (node (ref "R13") (pin "2") (pinfunction "2_2") (pintype "passive"))
      (node (ref "R21") (pin "2") (pinfunction "2_2") (pintype "passive"))
    )
    (net (code "54") (name "unconnected-(J2-4-PadP4)") (class "Default")
      (node (ref "J2") (pin "P4") (pinfunction "4_P4") (pintype "bidirectional"))
    )
    (net (code "55") (name "unconnected-(J2-6-PadP6)") (class "Default")
      (node (ref "J2") (pin "P6") (pinfunction "6_P6") (pintype "bidirectional"))
    )
    (net (code "56") (name "unconnected-(J3-SWO-Pad6)") (class "Default")
      (node (ref "J3") (pin "6") (pinfunction "SWO_6") (pintype "bidirectional"))
    )
    (net (code "57") (name "unconnected-(J3-~{RESET}-Pad3)") (class "Default")
      (node (ref "J3") (pin "3") (pinfunction "~{RESET}_3") (pintype "bidirectional"))
    )
    (net (code "58") (name "unconnected-(U4-P00{slash}AREF0-Pad4)") (class "Default")
      (node (ref "U4") (pin "4") (pinfunction "P00/AREF0_4") (pintype "bidirectional"))
    )
    (net (code "59") (name "unconnected-(U4-P01{slash}AIN2-Pad5)") (class "Default")
      (node (ref "U4") (pin "5") (pinfunction "P01/AIN2_5") (pintype "bidirectional"))
    )
    (net (code "60") (name "unconnected-(U4-P02{slash}AIN3-Pad6)") (class "Default")
      (node (ref "U4") (pin "6") (pinfunction "P02/AIN3_6") (pintype "bidirectional"))
    )
    (net (code "61") (name "unconnected-(U4-P03{slash}AIN4-Pad7)") (class "Default")
      (node (ref "U4") (pin "7") (pinfunction "P03/AIN4_7") (pintype "bidirectional"))
    )
    (net (code "62") (name "unconnected-(U4-P04{slash}AIN5-Pad8)") (class "Default")
      (node (ref "U4") (pin "8") (pinfunction "P04/AIN5_8") (pintype "bidirectional"))
    )
    (net (code "63") (name "unconnected-(U4-P06{slash}AIN7{slash}AREF1-Pad10)") (class "Default")
      (node (ref "U4") (pin "10") (pinfunction "P06/AIN7/AREF1_10") (pintype "bidirectional"))
    )
    (net (code "64") (name "unconnected-(U4-P07-Pad11)") (class "Default")
      (node (ref "U4") (pin "11") (pinfunction "P07_11") (pintype "bidirectional"))
    )
    (net (code "65") (name "unconnected-(U4-P08-Pad14)") (class "Default")
      (node (ref "U4") (pin "14") (pinfunction "P08_14") (pintype "bidirectional"))
    )
    (net (code "66") (name "unconnected-(U4-P09-Pad15)") (class "Default")
      (node (ref "U4") (pin "15") (pinfunction "P09_15") (pintype "bidirectional"))
    )
    (net (code "67") (name "unconnected-(U4-P10-Pad16)") (class "Default")
      (node (ref "U4") (pin "16") (pinfunction "P10_16") (pintype "bidirectional"))
    )
    (net (code "68") (name "unconnected-(U4-P11-Pad17)") (class "Default")
      (node (ref "U4") (pin "17") (pinfunction "P11_17") (pintype "bidirectional"))
    )
    (net (code "69") (name "unconnected-(U4-P12-Pad18)") (class "Default")
      (node (ref "U4") (pin "18") (pinfunction "P12_18") (pintype "bidirectional"))
    )
    (net (code "70") (name "unconnected-(U4-P13-Pad19)") (class "Default")
      (node (ref "U4") (pin "19") (pinfunction "P13_19") (pintype "bidirectional"))
    )
    (net (code "71") (name "unconnected-(U4-P14-Pad20)") (class "Default")
      (node (ref "U4") (pin "20") (pinfunction "P14_20") (pintype "bidirectional"))
    )
    (net (code "72") (name "unconnected-(U4-P15-Pad21)") (class "Default")
      (node (ref "U4") (pin "21") (pinfunction "P15_21") (pintype "bidirectional"))
    )
    (net (code "73") (name "unconnected-(U4-P16-Pad22)") (class "Default")
      (node (ref "U4") (pin "22") (pinfunction "P16_22") (pintype "bidirectional"))
    )
    (net (code "74") (name "unconnected-(U4-P17-Pad25)") (class "Default")
      (node (ref "U4") (pin "25") (pinfunction "P17_25") (pintype "bidirectional"))
    )
    (net (code "75") (name "unconnected-(U4-P18-Pad26)") (class "Default")
      (node (ref "U4") (pin "26") (pinfunction "P18_26") (pintype "bidirectional"))
    )
    (net (code "76") (name "unconnected-(U4-P19-Pad27)") (class "Default")
      (node (ref "U4") (pin "27") (pinfunction "P19_27") (pintype "bidirectional"))
    )
    (net (code "77") (name "unconnected-(U4-P20-Pad28)") (class "Default")
      (node (ref "U4") (pin "28") (pinfunction "P20_28") (pintype "bidirectional"))
    )
    (net (code "78") (name "unconnected-(U4-P21-Pad40)") (class "Default")
      (node (ref "U4") (pin "40") (pinfunction "P21_40") (pintype "bidirectional"))
    )
    (net (code "79") (name "unconnected-(U4-P22-Pad41)") (class "Default")
      (node (ref "U4") (pin "41") (pinfunction "P22_41") (pintype "bidirectional"))
    )
    (net (code "80") (name "unconnected-(U4-P23-Pad42)") (class "Default")
      (node (ref "U4") (pin "42") (pinfunction "P23_42") (pintype "bidirectional"))
    )
    (net (code "81") (name "unconnected-(U4-P24-Pad43)") (class "Default")
      (node (ref "U4") (pin "43") (pinfunction "P24_43") (pintype "bidirectional"))
    )
    (net (code "82") (name "unconnected-(U4-P25-Pad44)") (class "Default")
      (node (ref "U4") (pin "44") (pinfunction "P25_44") (pintype "bidirectional"))
    )
    (net (code "83") (name "unconnected-(U4-P26{slash}AIN0{slash}XL2-Pad45)") (class "Default")
      (node (ref "U4") (pin "45") (pinfunction "P26/AIN0/XL2_45") (pintype "bidirectional"))
    )
    (net (code "84") (name "unconnected-(U4-P30-Pad3)") (class "Default")
      (node (ref "U4") (pin "3") (pinfunction "P30_3") (pintype "bidirectional"))
    )
  )
)
